# bottom_3-28-21.net
KiCad netlist of a schematic drawn in EAGLE
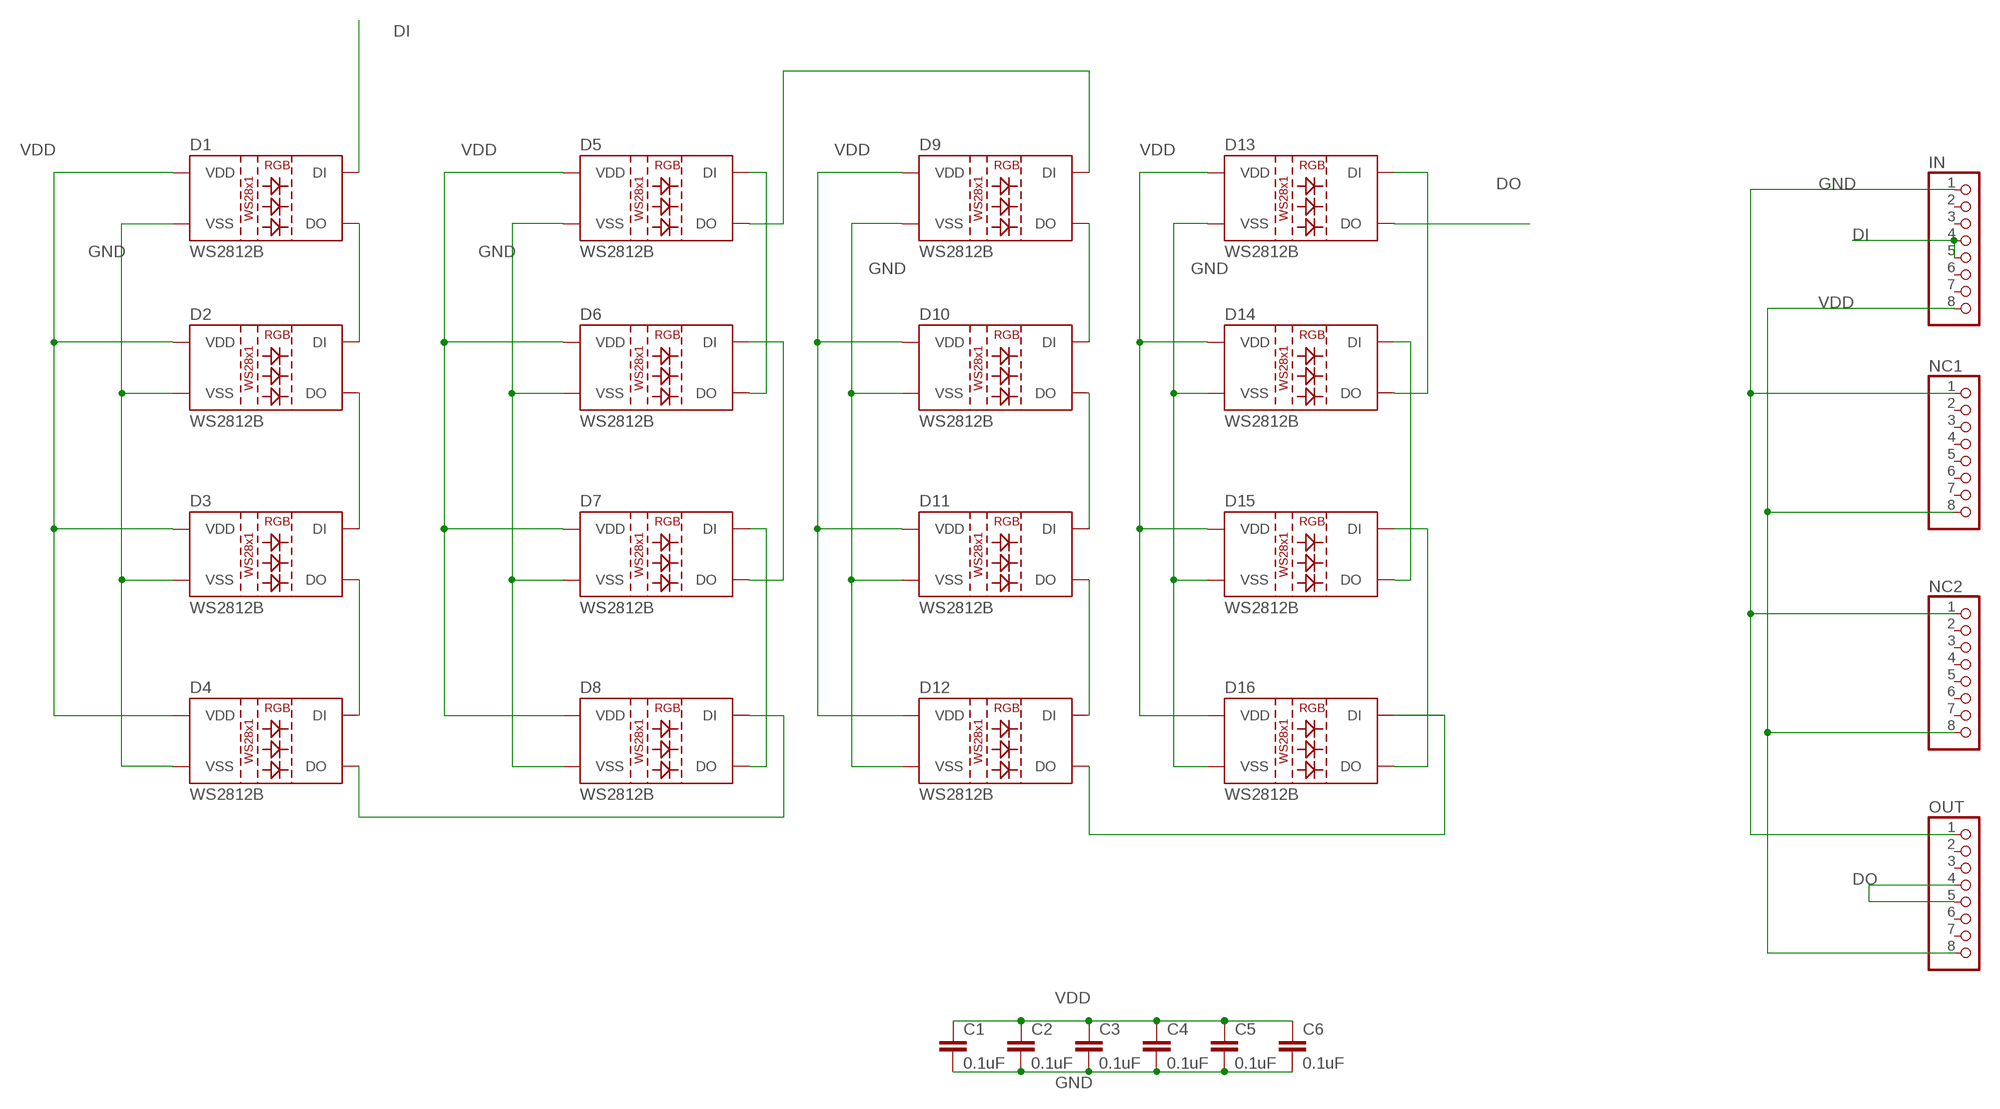
[diagram p0: schematic, sheet 1]

(export (version "E")
  (design (tool "Eeschema 10.0.6"))
  (components
    (comp (ref "C1")
      (value "0.1uF")
      (footprint "eagle-import:0603")
      (libsource (lib "eagle-import") (part "0.1UF-0603-25V-5%"))
    )
    (comp (ref "C2")
      (value "0.1uF")
      (footprint "eagle-import:0603")
      (libsource (lib "eagle-import") (part "0.1UF-0603-25V-5%"))
    )
    (comp (ref "C3")
      (value "0.1uF")
      (footprint "eagle-import:0603")
      (libsource (lib "eagle-import") (part "0.1UF-0603-25V-5%"))
    )
    (comp (ref "C4")
      (value "0.1uF")
      (footprint "eagle-import:0603")
      (libsource (lib "eagle-import") (part "0.1UF-0603-25V-5%"))
    )
    (comp (ref "C5")
      (value "0.1uF")
      (footprint "eagle-import:0603")
      (libsource (lib "eagle-import") (part "0.1UF-0603-25V-5%"))
    )
    (comp (ref "C6")
      (value "0.1uF")
      (footprint "eagle-import:0603")
      (libsource (lib "eagle-import") (part "0.1UF-0603-25V-5%"))
    )
    (comp (ref "D1")
      (value "WS2812B")
      (footprint "eagle-import:WS2812B")
      (libsource (lib "eagle-import") (part "WS2812B"))
    )
    (comp (ref "D2")
      (value "WS2812B")
      (footprint "eagle-import:WS2812B")
      (libsource (lib "eagle-import") (part "WS2812B"))
    )
    (comp (ref "D3")
      (value "WS2812B")
      (footprint "eagle-import:WS2812B")
      (libsource (lib "eagle-import") (part "WS2812B"))
    )
    (comp (ref "D4")
      (value "WS2812B")
      (footprint "eagle-import:WS2812B")
      (libsource (lib "eagle-import") (part "WS2812B"))
    )
    (comp (ref "D5")
      (value "WS2812B")
      (footprint "eagle-import:WS2812B")
      (libsource (lib "eagle-import") (part "WS2812B"))
    )
    (comp (ref "D6")
      (value "WS2812B")
      (footprint "eagle-import:WS2812B")
      (libsource (lib "eagle-import") (part "WS2812B"))
    )
    (comp (ref "D7")
      (value "WS2812B")
      (footprint "eagle-import:WS2812B")
      (libsource (lib "eagle-import") (part "WS2812B"))
    )
    (comp (ref "D8")
      (value "WS2812B")
      (footprint "eagle-import:WS2812B")
      (libsource (lib "eagle-import") (part "WS2812B"))
    )
    (comp (ref "D9")
      (value "WS2812B")
      (footprint "eagle-import:WS2812B")
      (libsource (lib "eagle-import") (part "WS2812B"))
    )
    (comp (ref "D10")
      (value "WS2812B")
      (footprint "eagle-import:WS2812B")
      (libsource (lib "eagle-import") (part "WS2812B"))
    )
    (comp (ref "D11")
      (value "WS2812B")
      (footprint "eagle-import:WS2812B")
      (libsource (lib "eagle-import") (part "WS2812B"))
    )
    (comp (ref "D12")
      (value "WS2812B")
      (footprint "eagle-import:WS2812B")
      (libsource (lib "eagle-import") (part "WS2812B"))
    )
    (comp (ref "D13")
      (value "WS2812B")
      (footprint "eagle-import:WS2812B")
      (libsource (lib "eagle-import") (part "WS2812B"))
    )
    (comp (ref "D14")
      (value "WS2812B")
      (footprint "eagle-import:WS2812B")
      (libsource (lib "eagle-import") (part "WS2812B"))
    )
    (comp (ref "D15")
      (value "WS2812B")
      (footprint "eagle-import:WS2812B")
      (libsource (lib "eagle-import") (part "WS2812B"))
    )
    (comp (ref "D16")
      (value "WS2812B")
      (footprint "eagle-import:WS2812B")
      (libsource (lib "eagle-import") (part "WS2812B"))
    )
    (comp (ref "IN")
      (value "PINHD-1X8")
      (footprint "eagle-import:1X08")
      (libsource (lib "eagle-import") (part "PINHD-1X8"))
    )
    (comp (ref "NC1")
      (value "PINHD-1X8")
      (footprint "eagle-import:1X08")
      (libsource (lib "eagle-import") (part "PINHD-1X8"))
    )
    (comp (ref "NC2")
      (value "PINHD-1X8")
      (footprint "eagle-import:1X08")
      (libsource (lib "eagle-import") (part "PINHD-1X8"))
    )
    (comp (ref "OUT")
      (value "PINHD-1X8")
      (footprint "eagle-import:1X08")
      (libsource (lib "eagle-import") (part "PINHD-1X8"))
    )
  )
  (nets
    (net (code "1") (name "/DI") (class "Default")
      (node (ref "D1") (pin "4") (pinfunction "DI_4") (pintype "bidirectional"))
      (node (ref "IN") (pin "4") (pinfunction "4_4") (pintype "passive"))
      (node (ref "IN") (pin "5") (pinfunction "5_5") (pintype "passive"))
    )
    (net (code "2") (name "/DO") (class "Default")
      (node (ref "D13") (pin "2") (pinfunction "DO_2") (pintype "bidirectional"))
      (node (ref "OUT") (pin "4") (pinfunction "4_4") (pintype "passive"))
      (node (ref "OUT") (pin "5") (pinfunction "5_5") (pintype "passive"))
    )
    (net (code "3") (name "/GND") (class "Default")
      (node (ref "C1") (pin "2") (pinfunction "2_2") (pintype "passive"))
      (node (ref "C2") (pin "2") (pinfunction "2_2") (pintype "passive"))
      (node (ref "C3") (pin "2") (pinfunction "2_2") (pintype "passive"))
      (node (ref "C4") (pin "2") (pinfunction "2_2") (pintype "passive"))
      (node (ref "C5") (pin "2") (pinfunction "2_2") (pintype "passive"))
      (node (ref "C6") (pin "2") (pinfunction "2_2") (pintype "passive"))
      (node (ref "D1") (pin "3") (pinfunction "VSS_3") (pintype "bidirectional"))
      (node (ref "D10") (pin "3") (pinfunction "VSS_3") (pintype "bidirectional"))
      (node (ref "D11") (pin "3") (pinfunction "VSS_3") (pintype "bidirectional"))
      (node (ref "D12") (pin "3") (pinfunction "VSS_3") (pintype "bidirectional"))
      (node (ref "D13") (pin "3") (pinfunction "VSS_3") (pintype "bidirectional"))
      (node (ref "D14") (pin "3") (pinfunction "VSS_3") (pintype "bidirectional"))
      (node (ref "D15") (pin "3") (pinfunction "VSS_3") (pintype "bidirectional"))
      (node (ref "D16") (pin "3") (pinfunction "VSS_3") (pintype "bidirectional"))
      (node (ref "D2") (pin "3") (pinfunction "VSS_3") (pintype "bidirectional"))
      (node (ref "D3") (pin "3") (pinfunction "VSS_3") (pintype "bidirectional"))
      (node (ref "D4") (pin "3") (pinfunction "VSS_3") (pintype "bidirectional"))
      (node (ref "D5") (pin "3") (pinfunction "VSS_3") (pintype "bidirectional"))
      (node (ref "D6") (pin "3") (pinfunction "VSS_3") (pintype "bidirectional"))
      (node (ref "D7") (pin "3") (pinfunction "VSS_3") (pintype "bidirectional"))
      (node (ref "D8") (pin "3") (pinfunction "VSS_3") (pintype "bidirectional"))
      (node (ref "D9") (pin "3") (pinfunction "VSS_3") (pintype "bidirectional"))
      (node (ref "IN") (pin "1") (pinfunction "1_1") (pintype "passive"))
      (node (ref "NC1") (pin "1") (pinfunction "1_1") (pintype "passive"))
      (node (ref "NC2") (pin "1") (pinfunction "1_1") (pintype "passive"))
      (node (ref "OUT") (pin "1") (pinfunction "1_1") (pintype "passive"))
    )
    (net (code "4") (name "/VDD") (class "Default")
      (node (ref "C1") (pin "1") (pinfunction "1_1") (pintype "passive"))
      (node (ref "C2") (pin "1") (pinfunction "1_1") (pintype "passive"))
      (node (ref "C3") (pin "1") (pinfunction "1_1") (pintype "passive"))
      (node (ref "C4") (pin "1") (pinfunction "1_1") (pintype "passive"))
      (node (ref "C5") (pin "1") (pinfunction "1_1") (pintype "passive"))
      (node (ref "C6") (pin "1") (pinfunction "1_1") (pintype "passive"))
      (node (ref "D1") (pin "1") (pinfunction "VDD_1") (pintype "bidirectional"))
      (node (ref "D10") (pin "1") (pinfunction "VDD_1") (pintype "bidirectional"))
      (node (ref "D11") (pin "1") (pinfunction "VDD_1") (pintype "bidirectional"))
      (node (ref "D12") (pin "1") (pinfunction "VDD_1") (pintype "bidirectional"))
      (node (ref "D13") (pin "1") (pinfunction "VDD_1") (pintype "bidirectional"))
      (node (ref "D14") (pin "1") (pinfunction "VDD_1") (pintype "bidirectional"))
      (node (ref "D15") (pin "1") (pinfunction "VDD_1") (pintype "bidirectional"))
      (node (ref "D16") (pin "1") (pinfunction "VDD_1") (pintype "bidirectional"))
      (node (ref "D2") (pin "1") (pinfunction "VDD_1") (pintype "bidirectional"))
      (node (ref "D3") (pin "1") (pinfunction "VDD_1") (pintype "bidirectional"))
      (node (ref "D4") (pin "1") (pinfunction "VDD_1") (pintype "bidirectional"))
      (node (ref "D5") (pin "1") (pinfunction "VDD_1") (pintype "bidirectional"))
      (node (ref "D6") (pin "1") (pinfunction "VDD_1") (pintype "bidirectional"))
      (node (ref "D7") (pin "1") (pinfunction "VDD_1") (pintype "bidirectional"))
      (node (ref "D8") (pin "1") (pinfunction "VDD_1") (pintype "bidirectional"))
      (node (ref "D9") (pin "1") (pinfunction "VDD_1") (pintype "bidirectional"))
      (node (ref "IN") (pin "8") (pinfunction "8_8") (pintype "passive"))
      (node (ref "NC1") (pin "8") (pinfunction "8_8") (pintype "passive"))
      (node (ref "NC2") (pin "8") (pinfunction "8_8") (pintype "passive"))
      (node (ref "OUT") (pin "8") (pinfunction "8_8") (pintype "passive"))
    )
    (net (code "5") (name "Net-(D1-DO)") (class "Default")
      (node (ref "D1") (pin "2") (pinfunction "DO_2") (pintype "bidirectional"))
      (node (ref "D2") (pin "4") (pinfunction "DI_4") (pintype "bidirectional"))
    )
    (net (code "6") (name "Net-(D2-DO)") (class "Default")
      (node (ref "D2") (pin "2") (pinfunction "DO_2") (pintype "bidirectional"))
      (node (ref "D3") (pin "4") (pinfunction "DI_4") (pintype "bidirectional"))
    )
    (net (code "7") (name "Net-(D3-DO)") (class "Default")
      (node (ref "D3") (pin "2") (pinfunction "DO_2") (pintype "bidirectional"))
      (node (ref "D4") (pin "4") (pinfunction "DI_4") (pintype "bidirectional"))
    )
    (net (code "8") (name "Net-(D4-DO)") (class "Default")
      (node (ref "D4") (pin "2") (pinfunction "DO_2") (pintype "bidirectional"))
      (node (ref "D8") (pin "4") (pinfunction "DI_4") (pintype "bidirectional"))
    )
    (net (code "9") (name "Net-(D5-DI)") (class "Default")
      (node (ref "D5") (pin "4") (pinfunction "DI_4") (pintype "bidirectional"))
      (node (ref "D6") (pin "2") (pinfunction "DO_2") (pintype "bidirectional"))
    )
    (net (code "10") (name "Net-(D5-DO)") (class "Default")
      (node (ref "D5") (pin "2") (pinfunction "DO_2") (pintype "bidirectional"))
      (node (ref "D9") (pin "4") (pinfunction "DI_4") (pintype "bidirectional"))
    )
    (net (code "11") (name "Net-(D6-DI)") (class "Default")
      (node (ref "D6") (pin "4") (pinfunction "DI_4") (pintype "bidirectional"))
      (node (ref "D7") (pin "2") (pinfunction "DO_2") (pintype "bidirectional"))
    )
    (net (code "12") (name "Net-(D7-DI)") (class "Default")
      (node (ref "D7") (pin "4") (pinfunction "DI_4") (pintype "bidirectional"))
      (node (ref "D8") (pin "2") (pinfunction "DO_2") (pintype "bidirectional"))
    )
    (net (code "13") (name "Net-(D10-DI)") (class "Default")
      (node (ref "D10") (pin "4") (pinfunction "DI_4") (pintype "bidirectional"))
      (node (ref "D9") (pin "2") (pinfunction "DO_2") (pintype "bidirectional"))
    )
    (net (code "14") (name "Net-(D10-DO)") (class "Default")
      (node (ref "D10") (pin "2") (pinfunction "DO_2") (pintype "bidirectional"))
      (node (ref "D11") (pin "4") (pinfunction "DI_4") (pintype "bidirectional"))
    )
    (net (code "15") (name "Net-(D11-DO)") (class "Default")
      (node (ref "D11") (pin "2") (pinfunction "DO_2") (pintype "bidirectional"))
      (node (ref "D12") (pin "4") (pinfunction "DI_4") (pintype "bidirectional"))
    )
    (net (code "16") (name "Net-(D12-DO)") (class "Default")
      (node (ref "D12") (pin "2") (pinfunction "DO_2") (pintype "bidirectional"))
      (node (ref "D16") (pin "4") (pinfunction "DI_4") (pintype "bidirectional"))
    )
    (net (code "17") (name "Net-(D13-DI)") (class "Default")
      (node (ref "D13") (pin "4") (pinfunction "DI_4") (pintype "bidirectional"))
      (node (ref "D14") (pin "2") (pinfunction "DO_2") (pintype "bidirectional"))
    )
    (net (code "18") (name "Net-(D14-DI)") (class "Default")
      (node (ref "D14") (pin "4") (pinfunction "DI_4") (pintype "bidirectional"))
      (node (ref "D15") (pin "2") (pinfunction "DO_2") (pintype "bidirectional"))
    )
    (net (code "19") (name "Net-(D15-DI)") (class "Default")
      (node (ref "D15") (pin "4") (pinfunction "DI_4") (pintype "bidirectional"))
      (node (ref "D16") (pin "2") (pinfunction "DO_2") (pintype "bidirectional"))
    )
    (net (code "20") (name "unconnected-(IN-Pad2)") (class "Default")
      (node (ref "IN") (pin "2") (pinfunction "2_2") (pintype "passive"))
    )
    (net (code "21") (name "unconnected-(IN-Pad3)") (class "Default")
      (node (ref "IN") (pin "3") (pinfunction "3_3") (pintype "passive"))
    )
    (net (code "22") (name "unconnected-(IN-Pad6)") (class "Default")
      (node (ref "IN") (pin "6") (pinfunction "6_6") (pintype "passive"))
    )
    (net (code "23") (name "unconnected-(IN-Pad7)") (class "Default")
      (node (ref "IN") (pin "7") (pinfunction "7_7") (pintype "passive"))
    )
    (net (code "24") (name "unconnected-(NC1-Pad2)") (class "Default")
      (node (ref "NC1") (pin "2") (pinfunction "2_2") (pintype "passive"))
    )
    (net (code "25") (name "unconnected-(NC1-Pad3)") (class "Default")
      (node (ref "NC1") (pin "3") (pinfunction "3_3") (pintype "passive"))
    )
    (net (code "26") (name "unconnected-(NC1-Pad4)") (class "Default")
      (node (ref "NC1") (pin "4") (pinfunction "4_4") (pintype "passive"))
    )
    (net (code "27") (name "unconnected-(NC1-Pad5)") (class "Default")
      (node (ref "NC1") (pin "5") (pinfunction "5_5") (pintype "passive"))
    )
    (net (code "28") (name "unconnected-(NC1-Pad6)") (class "Default")
      (node (ref "NC1") (pin "6") (pinfunction "6_6") (pintype "passive"))
    )
    (net (code "29") (name "unconnected-(NC1-Pad7)") (class "Default")
      (node (ref "NC1") (pin "7") (pinfunction "7_7") (pintype "passive"))
    )
    (net (code "30") (name "unconnected-(NC2-Pad2)") (class "Default")
      (node (ref "NC2") (pin "2") (pinfunction "2_2") (pintype "passive"))
    )
    (net (code "31") (name "unconnected-(NC2-Pad3)") (class "Default")
      (node (ref "NC2") (pin "3") (pinfunction "3_3") (pintype "passive"))
    )
    (net (code "32") (name "unconnected-(NC2-Pad4)") (class "Default")
      (node (ref "NC2") (pin "4") (pinfunction "4_4") (pintype "passive"))
    )
    (net (code "33") (name "unconnected-(NC2-Pad5)") (class "Default")
      (node (ref "NC2") (pin "5") (pinfunction "5_5") (pintype "passive"))
    )
    (net (code "34") (name "unconnected-(NC2-Pad6)") (class "Default")
      (node (ref "NC2") (pin "6") (pinfunction "6_6") (pintype "passive"))
    )
    (net (code "35") (name "unconnected-(NC2-Pad7)") (class "Default")
      (node (ref "NC2") (pin "7") (pinfunction "7_7") (pintype "passive"))
    )
    (net (code "36") (name "unconnected-(OUT-Pad2)") (class "Default")
      (node (ref "OUT") (pin "2") (pinfunction "2_2") (pintype "passive"))
    )
    (net (code "37") (name "unconnected-(OUT-Pad3)") (class "Default")
      (node (ref "OUT") (pin "3") (pinfunction "3_3") (pintype "passive"))
    )
    (net (code "38") (name "unconnected-(OUT-Pad6)") (class "Default")
      (node (ref "OUT") (pin "6") (pinfunction "6_6") (pintype "passive"))
    )
    (net (code "39") (name "unconnected-(OUT-Pad7)") (class "Default")
      (node (ref "OUT") (pin "7") (pinfunction "7_7") (pintype "passive"))
    )
  )
)
